# ADC_v1.net
KiCad netlist of a schematic drawn in EAGLE
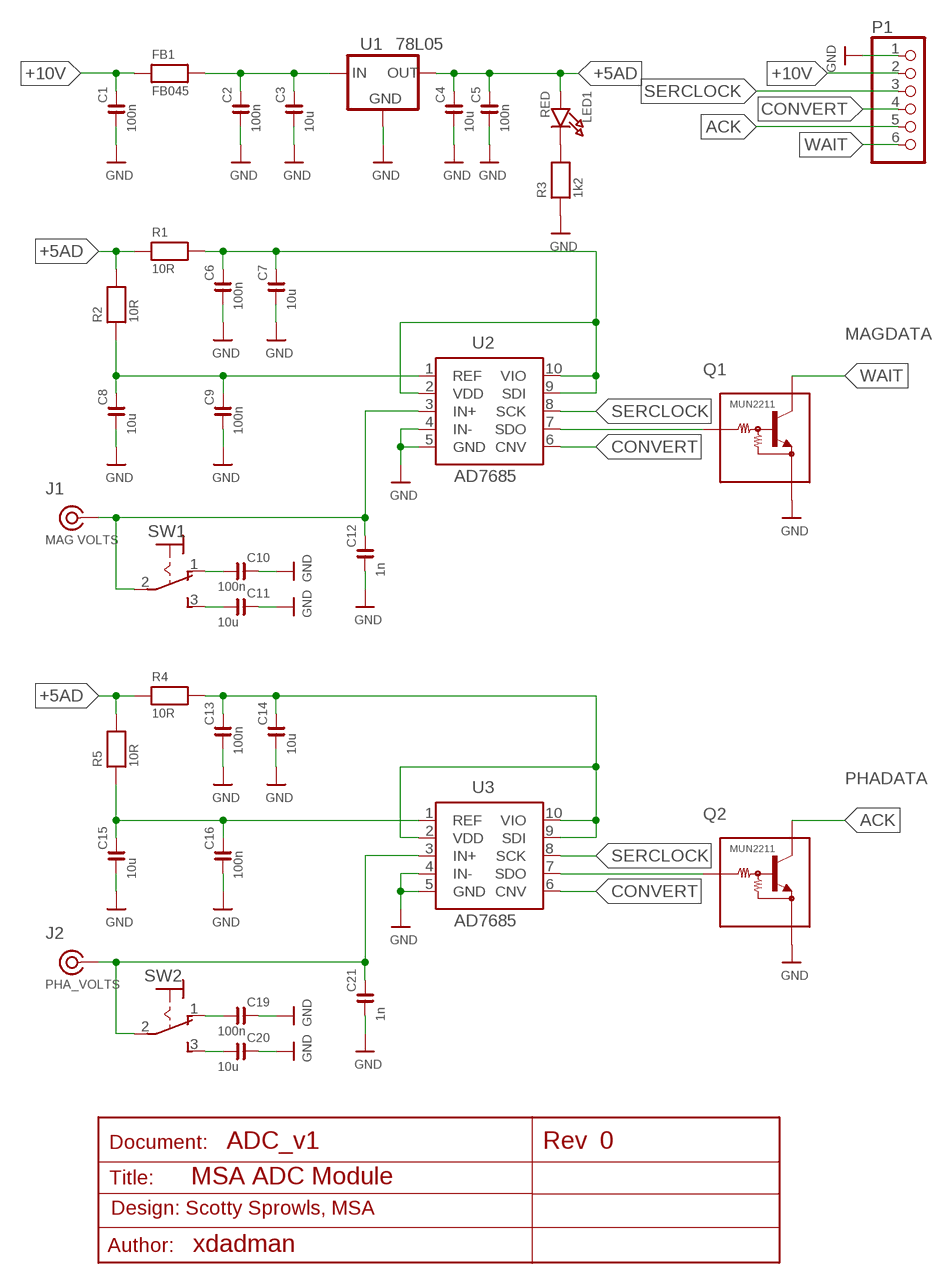
[diagram p0: schematic, sheet 1]

(export (version "E")
  (design (tool "Eeschema 10.0.6"))
  (components
    (comp (ref "C1")
      (value "100n")
      (footprint "eagle-import:C0805")
      (libsource (lib "eagle-import") (part "C0805100N"))
    )
    (comp (ref "C2")
      (value "100n")
      (footprint "eagle-import:C0805")
      (libsource (lib "eagle-import") (part "C0805100N"))
    )
    (comp (ref "C3")
      (value "10u")
      (footprint "eagle-import:C1206")
      (libsource (lib "eagle-import") (part "CC120610U"))
    )
    (comp (ref "C4")
      (value "10u")
      (footprint "eagle-import:C1206")
      (libsource (lib "eagle-import") (part "CC120610U"))
    )
    (comp (ref "C5")
      (value "100n")
      (footprint "eagle-import:C0805")
      (libsource (lib "eagle-import") (part "C0805100N"))
    )
    (comp (ref "C6")
      (value "100n")
      (footprint "eagle-import:C0805")
      (libsource (lib "eagle-import") (part "C0805100N"))
    )
    (comp (ref "C7")
      (value "10u")
      (footprint "eagle-import:C1206")
      (libsource (lib "eagle-import") (part "CC120610U"))
    )
    (comp (ref "C8")
      (value "10u")
      (footprint "eagle-import:C1206")
      (libsource (lib "eagle-import") (part "CC120610U"))
    )
    (comp (ref "C9")
      (value "100n")
      (footprint "eagle-import:C0805")
      (libsource (lib "eagle-import") (part "C0805100N"))
    )
    (comp (ref "C10")
      (value "100n")
      (footprint "eagle-import:C0805")
      (libsource (lib "eagle-import") (part "C0805100N"))
    )
    (comp (ref "C11")
      (value "10u")
      (footprint "eagle-import:C1206")
      (libsource (lib "eagle-import") (part "CC120610U"))
    )
    (comp (ref "C12")
      (value "1n")
      (footprint "eagle-import:C0805")
      (libsource (lib "eagle-import") (part "C08051N"))
    )
    (comp (ref "C13")
      (value "100n")
      (footprint "eagle-import:C0805")
      (libsource (lib "eagle-import") (part "C0805100N"))
    )
    (comp (ref "C14")
      (value "10u")
      (footprint "eagle-import:C1206")
      (libsource (lib "eagle-import") (part "CC120610U"))
    )
    (comp (ref "C15")
      (value "10u")
      (footprint "eagle-import:C1206")
      (libsource (lib "eagle-import") (part "CC120610U"))
    )
    (comp (ref "C16")
      (value "100n")
      (footprint "eagle-import:C0805")
      (libsource (lib "eagle-import") (part "C0805100N"))
    )
    (comp (ref "C19")
      (value "100n")
      (footprint "eagle-import:C0805")
      (libsource (lib "eagle-import") (part "C0805100N"))
    )
    (comp (ref "C20")
      (value "10u")
      (footprint "eagle-import:C1206")
      (libsource (lib "eagle-import") (part "CC120610U"))
    )
    (comp (ref "C21")
      (value "1n")
      (footprint "eagle-import:C0805")
      (libsource (lib "eagle-import") (part "C08051N"))
    )
    (comp (ref "FB1")
      (value "FB045")
      (footprint "eagle-import:R0805")
      (libsource (lib "eagle-import") (part "R0805FB045"))
    )
    (comp (ref "J1")
      (value "MAG VOLTS")
      (footprint "eagle-import:SLIM_COAX_PAD")
      (libsource (lib "eagle-import") (part "COAX"))
    )
    (comp (ref "J2")
      (value "PHA_VOLTS")
      (footprint "eagle-import:SLIM_COAX_PAD")
      (libsource (lib "eagle-import") (part "COAX"))
    )
    (comp (ref "LED1")
      (value "RED")
      (footprint "eagle-import:CHIPLED_0603")
      (libsource (lib "eagle-import") (part "LED_0603_RED0603"))
    )
    (comp (ref "P1")
      (value "PINHD-1X6")
      (footprint "eagle-import:1X06")
      (libsource (lib "eagle-import") (part "PINHD-1X6"))
    )
    (comp (ref "Q1")
      (value "MUN2211")
      (footprint "eagle-import:SOT23")
      (libsource (lib "eagle-import") (part "MUN2211"))
    )
    (comp (ref "Q2")
      (value "MUN2211")
      (footprint "eagle-import:SOT23")
      (libsource (lib "eagle-import") (part "MUN2211"))
    )
    (comp (ref "R1")
      (value "10R")
      (footprint "eagle-import:R0805")
      (libsource (lib "eagle-import") (part "R080510R"))
    )
    (comp (ref "R2")
      (value "10R")
      (footprint "eagle-import:R0805")
      (libsource (lib "eagle-import") (part "R080510R"))
    )
    (comp (ref "R3")
      (value "1k2")
      (footprint "eagle-import:R0805")
      (libsource (lib "eagle-import") (part "R08051K2"))
    )
    (comp (ref "R4")
      (value "10R")
      (footprint "eagle-import:R0805")
      (libsource (lib "eagle-import") (part "R080510R"))
    )
    (comp (ref "R5")
      (value "10R")
      (footprint "eagle-import:R0805")
      (libsource (lib "eagle-import") (part "R080510R"))
    )
    (comp (ref "SW1")
      (value "SWITCH1AS3")
      (footprint "eagle-import:1AS3T2B4M2RE")
      (libsource (lib "eagle-import") (part "SWITCH1AS3"))
    )
    (comp (ref "SW2")
      (value "SWITCH1AS3")
      (footprint "eagle-import:1AS3T2B4M2RE")
      (libsource (lib "eagle-import") (part "SWITCH1AS3"))
    )
    (comp (ref "U1")
      (value "78L05")
      (footprint "eagle-import:SOT89")
      (libsource (lib "eagle-import") (part "78MXXL78L05"))
    )
    (comp (ref "U2")
      (value "AD7685")
      (footprint "eagle-import:MSOP10")
      (libsource (lib "eagle-import") (part "AD7685"))
    )
    (comp (ref "U3")
      (value "AD7685")
      (footprint "eagle-import:MSOP10")
      (libsource (lib "eagle-import") (part "AD7685"))
    )
  )
  (nets
    (net (code "1") (name "+5AD") (class "Default")
      (node (ref "C4") (pin "2") (pinfunction "2_2") (pintype "passive"))
      (node (ref "C5") (pin "2") (pinfunction "2_2") (pintype "passive"))
      (node (ref "LED1") (pin "A") (pinfunction "A_A") (pintype "passive"))
      (node (ref "R1") (pin "1") (pinfunction "1_1") (pintype "passive"))
      (node (ref "R2") (pin "2") (pinfunction "2_2") (pintype "passive"))
      (node (ref "R4") (pin "1") (pinfunction "1_1") (pintype "passive"))
      (node (ref "R5") (pin "2") (pinfunction "2_2") (pintype "passive"))
      (node (ref "U1") (pin "1") (pinfunction "OUT_1") (pintype "passive"))
    )
    (net (code "2") (name "+10V") (class "Default")
      (node (ref "C1") (pin "2") (pinfunction "2_2") (pintype "passive"))
      (node (ref "FB1") (pin "1") (pinfunction "1_1") (pintype "passive"))
      (node (ref "P1") (pin "2") (pinfunction "2_2") (pintype "passive"))
    )
    (net (code "3") (name "ACK") (class "Default")
      (node (ref "P1") (pin "5") (pinfunction "5_5") (pintype "passive"))
      (node (ref "Q2") (pin "C") (pinfunction "C_C") (pintype "passive"))
    )
    (net (code "4") (name "CONVERT") (class "Default")
      (node (ref "P1") (pin "4") (pinfunction "4_4") (pintype "passive"))
      (node (ref "U2") (pin "6") (pinfunction "CNV_6") (pintype "input"))
      (node (ref "U3") (pin "6") (pinfunction "CNV_6") (pintype "input"))
    )
    (net (code "5") (name "GND") (class "Default")
      (node (ref "C1") (pin "1") (pinfunction "1_1") (pintype "passive"))
      (node (ref "C10") (pin "2") (pinfunction "2_2") (pintype "passive"))
      (node (ref "C11") (pin "2") (pinfunction "2_2") (pintype "passive"))
      (node (ref "C12") (pin "1") (pinfunction "1_1") (pintype "passive"))
      (node (ref "C13") (pin "1") (pinfunction "1_1") (pintype "passive"))
      (node (ref "C14") (pin "1") (pinfunction "1_1") (pintype "passive"))
      (node (ref "C15") (pin "1") (pinfunction "1_1") (pintype "passive"))
      (node (ref "C16") (pin "1") (pinfunction "1_1") (pintype "passive"))
      (node (ref "C19") (pin "2") (pinfunction "2_2") (pintype "passive"))
      (node (ref "C2") (pin "1") (pinfunction "1_1") (pintype "passive"))
      (node (ref "C20") (pin "2") (pinfunction "2_2") (pintype "passive"))
      (node (ref "C21") (pin "1") (pinfunction "1_1") (pintype "passive"))
      (node (ref "C3") (pin "1") (pinfunction "1_1") (pintype "passive"))
      (node (ref "C4") (pin "1") (pinfunction "1_1") (pintype "passive"))
      (node (ref "C5") (pin "1") (pinfunction "1_1") (pintype "passive"))
      (node (ref "C6") (pin "1") (pinfunction "1_1") (pintype "passive"))
      (node (ref "C7") (pin "1") (pinfunction "1_1") (pintype "passive"))
      (node (ref "C8") (pin "1") (pinfunction "1_1") (pintype "passive"))
      (node (ref "C9") (pin "1") (pinfunction "1_1") (pintype "passive"))
      (node (ref "P1") (pin "1") (pinfunction "1_1") (pintype "passive"))
      (node (ref "Q1") (pin "E") (pinfunction "E_E") (pintype "passive"))
      (node (ref "Q2") (pin "E") (pinfunction "E_E") (pintype "passive"))
      (node (ref "R3") (pin "1") (pinfunction "1_1") (pintype "passive"))
      (node (ref "U1") (pin "2") (pinfunction "GND_2") (pintype "input"))
      (node (ref "U1") (pin "4") (pinfunction "GND_4") (pintype "input"))
      (node (ref "U2") (pin "4") (pinfunction "IN-_4") (pintype "input"))
      (node (ref "U2") (pin "5") (pinfunction "GND_5") (pintype "power_in"))
      (node (ref "U3") (pin "4") (pinfunction "IN-_4") (pintype "input"))
      (node (ref "U3") (pin "5") (pinfunction "GND_5") (pintype "power_in"))
    )
    (net (code "6") (name "Net-(J1A-1)") (class "Default")
      (node (ref "C12") (pin "2") (pinfunction "2_2") (pintype "passive"))
      (node (ref "J1") (pin "SIG") (pinfunction "1_SIG") (pintype "passive"))
      (node (ref "SW1") (pin "2") (pinfunction "P_2") (pintype "passive"))
      (node (ref "U2") (pin "3") (pinfunction "IN+_3") (pintype "input"))
    )
    (net (code "7") (name "Net-(J2A-1)") (class "Default")
      (node (ref "C21") (pin "2") (pinfunction "2_2") (pintype "passive"))
      (node (ref "J2") (pin "SIG") (pinfunction "1_SIG") (pintype "passive"))
      (node (ref "SW2") (pin "2") (pinfunction "P_2") (pintype "passive"))
      (node (ref "U3") (pin "3") (pinfunction "IN+_3") (pintype "input"))
    )
    (net (code "8") (name "Net-(LED1-PadC)") (class "Default")
      (node (ref "LED1") (pin "C") (pinfunction "C_C") (pintype "passive"))
      (node (ref "R3") (pin "2") (pinfunction "2_2") (pintype "passive"))
    )
    (net (code "9") (name "Net-(SW1-O)") (class "Default")
      (node (ref "C10") (pin "1") (pinfunction "1_1") (pintype "passive"))
      (node (ref "SW1") (pin "1") (pinfunction "O_1") (pintype "passive"))
    )
    (net (code "10") (name "Net-(SW1-S)") (class "Default")
      (node (ref "C11") (pin "1") (pinfunction "1_1") (pintype "passive"))
      (node (ref "SW1") (pin "3") (pinfunction "S_3") (pintype "passive"))
    )
    (net (code "11") (name "Net-(SW2-O)") (class "Default")
      (node (ref "C19") (pin "1") (pinfunction "1_1") (pintype "passive"))
      (node (ref "SW2") (pin "1") (pinfunction "O_1") (pintype "passive"))
    )
    (net (code "12") (name "Net-(SW2-S)") (class "Default")
      (node (ref "C20") (pin "1") (pinfunction "1_1") (pintype "passive"))
      (node (ref "SW2") (pin "3") (pinfunction "S_3") (pintype "passive"))
    )
    (net (code "13") (name "Net-(U1-IN)") (class "Default")
      (node (ref "C2") (pin "2") (pinfunction "2_2") (pintype "passive"))
      (node (ref "C3") (pin "2") (pinfunction "2_2") (pintype "passive"))
      (node (ref "FB1") (pin "2") (pinfunction "2_2") (pintype "passive"))
      (node (ref "U1") (pin "3") (pinfunction "IN_3") (pintype "input"))
    )
    (net (code "14") (name "Net-(U2-REF)") (class "Default")
      (node (ref "C8") (pin "2") (pinfunction "2_2") (pintype "passive"))
      (node (ref "C9") (pin "2") (pinfunction "2_2") (pintype "passive"))
      (node (ref "R2") (pin "1") (pinfunction "1_1") (pintype "passive"))
      (node (ref "U2") (pin "1") (pinfunction "REF_1") (pintype "input"))
    )
    (net (code "15") (name "Net-(U2-SDI)") (class "Default")
      (node (ref "C6") (pin "2") (pinfunction "2_2") (pintype "passive"))
      (node (ref "C7") (pin "2") (pinfunction "2_2") (pintype "passive"))
      (node (ref "R1") (pin "2") (pinfunction "2_2") (pintype "passive"))
      (node (ref "U2") (pin "10") (pinfunction "VIO_10") (pintype "power_in"))
      (node (ref "U2") (pin "2") (pinfunction "VDD_2") (pintype "power_in"))
      (node (ref "U2") (pin "9") (pinfunction "SDI_9") (pintype "input"))
    )
    (net (code "16") (name "Net-(U2-SDO)") (class "Default")
      (node (ref "Q1") (pin "B") (pinfunction "B_B") (pintype "passive"))
      (node (ref "U2") (pin "7") (pinfunction "SDO_7") (pintype "output"))
    )
    (net (code "17") (name "Net-(U3-REF)") (class "Default")
      (node (ref "C15") (pin "2") (pinfunction "2_2") (pintype "passive"))
      (node (ref "C16") (pin "2") (pinfunction "2_2") (pintype "passive"))
      (node (ref "R5") (pin "1") (pinfunction "1_1") (pintype "passive"))
      (node (ref "U3") (pin "1") (pinfunction "REF_1") (pintype "input"))
    )
    (net (code "18") (name "Net-(U3-SDI)") (class "Default")
      (node (ref "C13") (pin "2") (pinfunction "2_2") (pintype "passive"))
      (node (ref "C14") (pin "2") (pinfunction "2_2") (pintype "passive"))
      (node (ref "R4") (pin "2") (pinfunction "2_2") (pintype "passive"))
      (node (ref "U3") (pin "10") (pinfunction "VIO_10") (pintype "power_in"))
      (node (ref "U3") (pin "2") (pinfunction "VDD_2") (pintype "power_in"))
      (node (ref "U3") (pin "9") (pinfunction "SDI_9") (pintype "input"))
    )
    (net (code "19") (name "Net-(U3-SDO)") (class "Default")
      (node (ref "Q2") (pin "B") (pinfunction "B_B") (pintype "passive"))
      (node (ref "U3") (pin "7") (pinfunction "SDO_7") (pintype "output"))
    )
    (net (code "20") (name "SERCLOCK") (class "Default")
      (node (ref "P1") (pin "3") (pinfunction "3_3") (pintype "passive"))
      (node (ref "U2") (pin "8") (pinfunction "SCK_8") (pintype "input"))
      (node (ref "U3") (pin "8") (pinfunction "SCK_8") (pintype "input"))
    )
    (net (code "21") (name "WAIT") (class "Default")
      (node (ref "P1") (pin "6") (pinfunction "6_6") (pintype "passive"))
      (node (ref "Q1") (pin "C") (pinfunction "C_C") (pintype "passive"))
    )
  )
)
